# WAVE_RESHAPE.net
KiCad netlist of a schematic drawn in Altium Designer
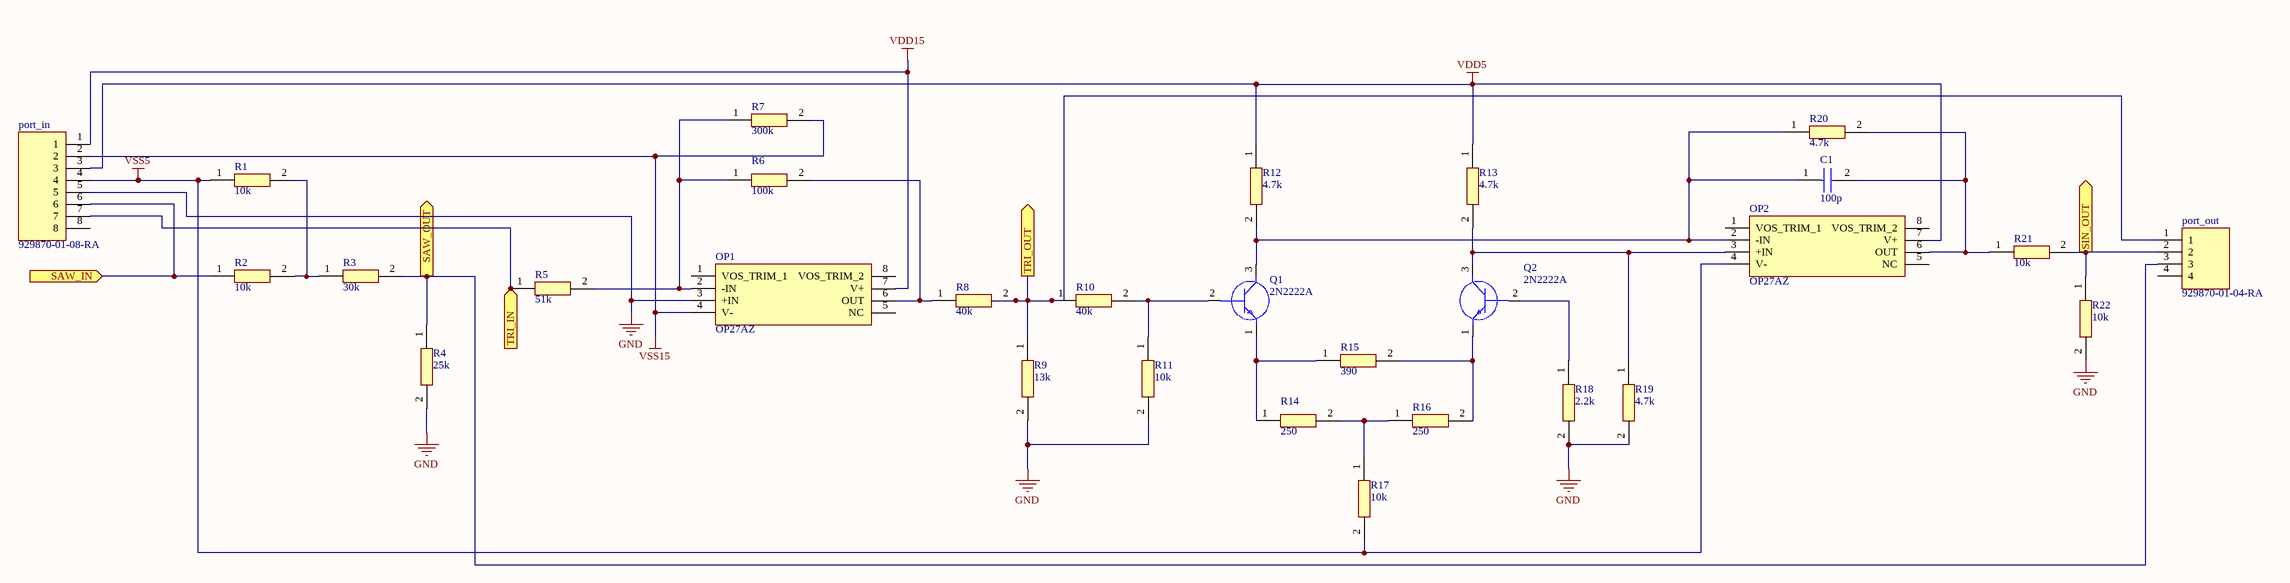
[diagram p0: WAVE_RESHAPE.SchDoc]

(export (version "E")
  (design (tool "Eeschema 10.0.6"))
  (components
    (comp (ref "C1")
      (value "100p")
      (footprint "SamacSys:CAPPA2400W30L800D400")
      (description "Capacitor")
      (fields (field (name "MANUFACTURER_PART_NUMBER") "0113207"))
      (libsource (lib "SamacSys") (part "0113207"))
    )
    (comp (ref "OP1")
      (value "OP27AZ")
      (footprint "SamacSys:DIP775W58P254L1029H508Q8N")
      (description "Integrated Circuit")
      (fields (field (name "MOUSER PART NUMBER") "700-OP27AZNR"))
      (libsource (lib "*") (part "OP27AZ"))
    )
    (comp (ref "OP2")
      (value "OP27AZ")
      (footprint "SamacSys:DIP775W58P254L1029H508Q8N")
      (description "Integrated Circuit")
      (fields (field (name "MOUSER PART NUMBER") "700-OP27AZNR"))
      (libsource (lib "SamacSys") (part "OP27AZ"))
    )
    (comp (ref "port_in")
      (value "929870-01-08-RA")
      (footprint "SamacSys:929870-01-08-RA")
      (description "Connector")
      (fields (field (name "MOUSER PART NUMBER") "517-929870-01-08-RA"))
      (libsource (lib "SamacSys") (part "929870-01-08-RA"))
    )
    (comp (ref "port_out")
      (value "929870-01-04-RA")
      (footprint "SamacSys:RHDR4W76P0X254_1X4_1016X254X826P")
      (description "Connector")
      (fields (field (name "MOUSER PART NUMBER") "517-929870-01-04-RA"))
      (libsource (lib "SamacSys") (part "929870-01-04-RA"))
    )
    (comp (ref "Q1")
      (value "2N2222A")
      (footprint "SamacSys:CENTRAL_TO18")
      (description "Transistor BJT NPN")
      (fields (field (name "MOUSER PART NUMBER") "610-2N2222A"))
      (libsource (lib "*") (part "2N2222A"))
    )
    (comp (ref "Q2")
      (value "2N2222A")
      (footprint "SamacSys:CENTRAL_TO18")
      (description "Transistor BJT NPN")
      (fields (field (name "MOUSER PART NUMBER") "610-2N2222A"))
      (libsource (lib "SamacSys") (part "2N2222A"))
    )
    (comp (ref "R1")
      (value "10k")
      (footprint "SamacSys:RESAD1650W60L650D250")
      (description "Resistor")
      (fields
        (field (name "MANUFACTURER_PART_NUMBER") "MRS25000C1003FC100")
        (field (name "MOUSER PART NUMBER") "594-MRS25000C1003FC1")
      )
      (libsource (lib "SamacSys") (part "MRS25000C1003FC100"))
    )
    (comp (ref "R2")
      (value "10k")
      (footprint "SamacSys:RESAD1650W60L650D250")
      (description "Resistor")
      (fields
        (field (name "MANUFACTURER_PART_NUMBER") "MRS25000C1003FC100")
        (field (name "MOUSER PART NUMBER") "594-MRS25000C1003FC1")
      )
      (libsource (lib "SamacSys") (part "MRS25000C1003FC100"))
    )
    (comp (ref "R3")
      (value "30k")
      (footprint "SamacSys:RESAD1650W60L650D250")
      (description "Resistor")
      (fields
        (field (name "MANUFACTURER_PART_NUMBER") "MRS25000C1003FC100")
        (field (name "MOUSER PART NUMBER") "594-MRS25000C1003FC1")
      )
      (libsource (lib "SamacSys") (part "MRS25000C1003FC100"))
    )
    (comp (ref "R4")
      (value "25k")
      (footprint "SamacSys:RESAD1650W60L650D250")
      (description "Resistor")
      (fields
        (field (name "MANUFACTURER_PART_NUMBER") "MRS25000C1003FC100")
        (field (name "MOUSER PART NUMBER") "594-MRS25000C1003FC1")
      )
      (libsource (lib "") (part "MRS25000C1003FC100_1"))
    )
    (comp (ref "R5")
      (value "51k")
      (footprint "SamacSys:RESAD1650W60L650D250")
      (description "Resistor")
      (fields
        (field (name "MANUFACTURER_PART_NUMBER") "MRS25000C1003FC100")
        (field (name "MOUSER PART NUMBER") "594-MRS25000C1003FC1")
      )
      (libsource (lib "SamacSys") (part "MRS25000C1003FC100"))
    )
    (comp (ref "R6")
      (value "100k")
      (footprint "SamacSys:RESAD1650W60L650D250")
      (description "Resistor")
      (fields
        (field (name "MANUFACTURER_PART_NUMBER") "MRS25000C1003FC100")
        (field (name "MOUSER PART NUMBER") "594-MRS25000C1003FC1")
      )
      (libsource (lib "SamacSys") (part "MRS25000C1003FC100"))
    )
    (comp (ref "R7")
      (value "300k")
      (footprint "SamacSys:RESAD1650W60L650D250")
      (description "Resistor")
      (fields
        (field (name "MANUFACTURER_PART_NUMBER") "MRS25000C1003FC100")
        (field (name "MOUSER PART NUMBER") "594-MRS25000C1003FC1")
      )
      (libsource (lib "SamacSys") (part "MRS25000C1003FC100"))
    )
    (comp (ref "R8")
      (value "40k")
      (footprint "SamacSys:RESAD1650W60L650D250")
      (description "Resistor")
      (fields
        (field (name "MANUFACTURER_PART_NUMBER") "MRS25000C1003FC100")
        (field (name "MOUSER PART NUMBER") "594-MRS25000C1003FC1")
      )
      (libsource (lib "SamacSys") (part "MRS25000C1003FC100"))
    )
    (comp (ref "R9")
      (value "13k")
      (footprint "SamacSys:RESAD1650W60L650D250")
      (description "Resistor")
      (fields
        (field (name "MANUFACTURER_PART_NUMBER") "MRS25000C1003FC100")
        (field (name "MOUSER PART NUMBER") "594-MRS25000C1003FC1")
      )
      (libsource (lib "") (part "MRS25000C1003FC100_1"))
    )
    (comp (ref "R10")
      (value "40k")
      (footprint "SamacSys:RESAD1650W60L650D250")
      (description "Resistor")
      (fields
        (field (name "MANUFACTURER_PART_NUMBER") "MRS25000C1003FC100")
        (field (name "MOUSER PART NUMBER") "594-MRS25000C1003FC1")
      )
      (libsource (lib "SamacSys") (part "MRS25000C1003FC100"))
    )
    (comp (ref "R11")
      (value "10k")
      (footprint "SamacSys:RESAD1650W60L650D250")
      (description "Resistor")
      (fields
        (field (name "MANUFACTURER_PART_NUMBER") "MRS25000C1003FC100")
        (field (name "MOUSER PART NUMBER") "594-MRS25000C1003FC1")
      )
      (libsource (lib "") (part "MRS25000C1003FC100_1"))
    )
    (comp (ref "R12")
      (value "4.7k")
      (footprint "SamacSys:RESAD1650W60L650D250")
      (description "Resistor")
      (fields
        (field (name "MANUFACTURER_PART_NUMBER") "MRS25000C1003FC100")
        (field (name "MOUSER PART NUMBER") "594-MRS25000C1003FC1")
      )
      (libsource (lib "") (part "MRS25000C1003FC100_1"))
    )
    (comp (ref "R13")
      (value "4.7k")
      (footprint "SamacSys:RESAD1650W60L650D250")
      (description "Resistor")
      (fields
        (field (name "MANUFACTURER_PART_NUMBER") "MRS25000C1003FC100")
        (field (name "MOUSER PART NUMBER") "594-MRS25000C1003FC1")
      )
      (libsource (lib "") (part "MRS25000C1003FC100_1"))
    )
    (comp (ref "R14")
      (value "250")
      (footprint "SamacSys:RESAD1650W60L650D250")
      (description "Resistor")
      (fields
        (field (name "MANUFACTURER_PART_NUMBER") "MRS25000C1003FC100")
        (field (name "MOUSER PART NUMBER") "594-MRS25000C1003FC1")
      )
      (libsource (lib "SamacSys") (part "MRS25000C1003FC100"))
    )
    (comp (ref "R15")
      (value "390")
      (footprint "SamacSys:RESAD1650W60L650D250")
      (description "Resistor")
      (fields
        (field (name "MANUFACTURER_PART_NUMBER") "MRS25000C1003FC100")
        (field (name "MOUSER PART NUMBER") "594-MRS25000C1003FC1")
      )
      (libsource (lib "SamacSys") (part "MRS25000C1003FC100"))
    )
    (comp (ref "R16")
      (value "250")
      (footprint "SamacSys:RESAD1650W60L650D250")
      (description "Resistor")
      (fields
        (field (name "MANUFACTURER_PART_NUMBER") "MRS25000C1003FC100")
        (field (name "MOUSER PART NUMBER") "594-MRS25000C1003FC1")
      )
      (libsource (lib "SamacSys") (part "MRS25000C1003FC100"))
    )
    (comp (ref "R17")
      (value "10k")
      (footprint "SamacSys:RESAD1650W60L650D250")
      (description "Resistor")
      (fields
        (field (name "MANUFACTURER_PART_NUMBER") "MRS25000C1003FC100")
        (field (name "MOUSER PART NUMBER") "594-MRS25000C1003FC1")
      )
      (libsource (lib "") (part "MRS25000C1003FC100_1"))
    )
    (comp (ref "R18")
      (value "2.2k")
      (footprint "SamacSys:RESAD1650W60L650D250")
      (description "Resistor")
      (fields
        (field (name "MANUFACTURER_PART_NUMBER") "MRS25000C1003FC100")
        (field (name "MOUSER PART NUMBER") "594-MRS25000C1003FC1")
      )
      (libsource (lib "") (part "MRS25000C1003FC100_1"))
    )
    (comp (ref "R19")
      (value "4.7k")
      (footprint "SamacSys:RESAD1650W60L650D250")
      (description "Resistor")
      (fields
        (field (name "MANUFACTURER_PART_NUMBER") "MRS25000C1003FC100")
        (field (name "MOUSER PART NUMBER") "594-MRS25000C1003FC1")
      )
      (libsource (lib "") (part "MRS25000C1003FC100_1"))
    )
    (comp (ref "R20")
      (value "4.7k")
      (footprint "SamacSys:RESAD1650W60L650D250")
      (description "Resistor")
      (fields
        (field (name "MANUFACTURER_PART_NUMBER") "MRS25000C1003FC100")
        (field (name "MOUSER PART NUMBER") "594-MRS25000C1003FC1")
      )
      (libsource (lib "SamacSys") (part "MRS25000C1003FC100"))
    )
    (comp (ref "R21")
      (value "10k")
      (footprint "SamacSys:RESAD1650W60L650D250")
      (description "Resistor")
      (fields
        (field (name "MANUFACTURER_PART_NUMBER") "MRS25000C1003FC100")
        (field (name "MOUSER PART NUMBER") "594-MRS25000C1003FC1")
      )
      (libsource (lib "SamacSys") (part "MRS25000C1003FC100"))
    )
    (comp (ref "R22")
      (value "10k")
      (footprint "SamacSys:RESAD1650W60L650D250")
      (description "Resistor")
      (fields
        (field (name "MANUFACTURER_PART_NUMBER") "MRS25000C1003FC100")
        (field (name "MOUSER PART NUMBER") "594-MRS25000C1003FC1")
      )
      (libsource (lib "") (part "MRS25000C1003FC100_1"))
    )
  )
  (nets
    (net (code "1") (name "/SAW_IN") (class "Default")
      (node (ref "R2") (pin "1") (pinfunction "1_1") (pintype "passive"))
      (node (ref "port_in") (pin "6") (pinfunction "6_6") (pintype "passive"))
    )
    (net (code "2") (name "/SAW_OUT") (class "Default")
      (node (ref "R3") (pin "2") (pinfunction "2_2") (pintype "passive"))
      (node (ref "R4") (pin "1") (pinfunction "1_1") (pintype "passive"))
      (node (ref "port_out") (pin "3") (pinfunction "3_3") (pintype "passive"))
    )
    (net (code "3") (name "/SIN_OUT") (class "Default")
      (node (ref "R21") (pin "2") (pinfunction "2_2") (pintype "passive"))
      (node (ref "R22") (pin "1") (pinfunction "1_1") (pintype "passive"))
      (node (ref "port_out") (pin "2") (pinfunction "2_2") (pintype "passive"))
    )
    (net (code "4") (name "/TRI_IN") (class "Default")
      (node (ref "R5") (pin "1") (pinfunction "1_1") (pintype "passive"))
      (node (ref "port_in") (pin "7") (pinfunction "7_7") (pintype "passive"))
    )
    (net (code "5") (name "/TRI_OUT") (class "Default")
      (node (ref "R10") (pin "1") (pinfunction "1_1") (pintype "passive"))
      (node (ref "R8") (pin "2") (pinfunction "2_2") (pintype "passive"))
      (node (ref "R9") (pin "1") (pinfunction "1_1") (pintype "passive"))
      (node (ref "port_out") (pin "1") (pinfunction "1_1") (pintype "passive"))
    )
    (net (code "6") (name "GND") (class "Default")
      (node (ref "OP1") (pin "3") (pinfunction "+IN_3") (pintype "passive"))
      (node (ref "R11") (pin "2") (pinfunction "2_2") (pintype "passive"))
      (node (ref "R18") (pin "2") (pinfunction "2_2") (pintype "passive"))
      (node (ref "R19") (pin "2") (pinfunction "2_2") (pintype "passive"))
      (node (ref "R22") (pin "2") (pinfunction "2_2") (pintype "passive"))
      (node (ref "R4") (pin "2") (pinfunction "2_2") (pintype "passive"))
      (node (ref "R9") (pin "2") (pinfunction "2_2") (pintype "passive"))
      (node (ref "port_in") (pin "5") (pinfunction "5_5") (pintype "passive"))
    )
    (net (code "7") (name "Net-(C1-+)") (class "Default")
      (node (ref "C1") (pin "1") (pinfunction "+_1") (pintype "passive"))
      (node (ref "OP2") (pin "2") (pinfunction "-IN_2") (pintype "passive"))
      (node (ref "Q1") (pin "3") (pinfunction "C_3") (pintype "passive"))
      (node (ref "R12") (pin "2") (pinfunction "2_2") (pintype "passive"))
      (node (ref "R20") (pin "1") (pinfunction "1_1") (pintype "passive"))
    )
    (net (code "8") (name "Net-(C1--)") (class "Default")
      (node (ref "C1") (pin "2") (pinfunction "-_2") (pintype "passive"))
      (node (ref "OP2") (pin "6") (pinfunction "OUT_6") (pintype "passive"))
      (node (ref "R20") (pin "2") (pinfunction "2_2") (pintype "passive"))
      (node (ref "R21") (pin "1") (pinfunction "1_1") (pintype "passive"))
    )
    (net (code "9") (name "Net-(OP1--IN)") (class "Default")
      (node (ref "OP1") (pin "2") (pinfunction "-IN_2") (pintype "passive"))
      (node (ref "R5") (pin "2") (pinfunction "2_2") (pintype "passive"))
      (node (ref "R6") (pin "1") (pinfunction "1_1") (pintype "passive"))
      (node (ref "R7") (pin "1") (pinfunction "1_1") (pintype "passive"))
    )
    (net (code "10") (name "Net-(OP1-OUT)") (class "Default")
      (node (ref "OP1") (pin "6") (pinfunction "OUT_6") (pintype "passive"))
      (node (ref "R6") (pin "2") (pinfunction "2_2") (pintype "passive"))
      (node (ref "R8") (pin "1") (pinfunction "1_1") (pintype "passive"))
    )
    (net (code "11") (name "Net-(OP2-+IN)") (class "Default")
      (node (ref "OP2") (pin "3") (pinfunction "+IN_3") (pintype "passive"))
      (node (ref "Q2") (pin "3") (pinfunction "C_3") (pintype "passive"))
      (node (ref "R13") (pin "2") (pinfunction "2_2") (pintype "passive"))
      (node (ref "R19") (pin "1") (pinfunction "1_1") (pintype "passive"))
    )
    (net (code "12") (name "Net-(Q1-B)") (class "Default")
      (node (ref "Q1") (pin "2") (pinfunction "B_2") (pintype "passive"))
      (node (ref "R10") (pin "2") (pinfunction "2_2") (pintype "passive"))
      (node (ref "R11") (pin "1") (pinfunction "1_1") (pintype "passive"))
    )
    (net (code "13") (name "Net-(Q1-E)") (class "Default")
      (node (ref "Q1") (pin "1") (pinfunction "E_1") (pintype "passive"))
      (node (ref "R14") (pin "1") (pinfunction "1_1") (pintype "passive"))
      (node (ref "R15") (pin "1") (pinfunction "1_1") (pintype "passive"))
    )
    (net (code "14") (name "Net-(Q2-B)") (class "Default")
      (node (ref "Q2") (pin "2") (pinfunction "B_2") (pintype "passive"))
      (node (ref "R18") (pin "1") (pinfunction "1_1") (pintype "passive"))
    )
    (net (code "15") (name "Net-(Q2-E)") (class "Default")
      (node (ref "Q2") (pin "1") (pinfunction "E_1") (pintype "passive"))
      (node (ref "R15") (pin "2") (pinfunction "2_2") (pintype "passive"))
      (node (ref "R16") (pin "2") (pinfunction "2_2") (pintype "passive"))
    )
    (net (code "16") (name "Net-(R1-Pad2)") (class "Default")
      (node (ref "R1") (pin "2") (pinfunction "2_2") (pintype "passive"))
      (node (ref "R2") (pin "2") (pinfunction "2_2") (pintype "passive"))
      (node (ref "R3") (pin "1") (pinfunction "1_1") (pintype "passive"))
    )
    (net (code "17") (name "Net-(R14-Pad2)") (class "Default")
      (node (ref "R14") (pin "2") (pinfunction "2_2") (pintype "passive"))
      (node (ref "R16") (pin "1") (pinfunction "1_1") (pintype "passive"))
      (node (ref "R17") (pin "1") (pinfunction "1_1") (pintype "passive"))
    )
    (net (code "18") (name "VDD5") (class "Default")
      (node (ref "OP2") (pin "7") (pinfunction "V+_7") (pintype "passive"))
      (node (ref "R12") (pin "1") (pinfunction "1_1") (pintype "passive"))
      (node (ref "R13") (pin "1") (pinfunction "1_1") (pintype "passive"))
      (node (ref "port_in") (pin "3") (pinfunction "3_3") (pintype "passive"))
    )
    (net (code "19") (name "VDD15") (class "Default")
      (node (ref "OP1") (pin "7") (pinfunction "V+_7") (pintype "passive"))
      (node (ref "port_in") (pin "1") (pinfunction "1_1") (pintype "passive"))
    )
    (net (code "20") (name "VSS5") (class "Default")
      (node (ref "OP2") (pin "4") (pinfunction "V-_4") (pintype "passive"))
      (node (ref "R1") (pin "1") (pinfunction "1_1") (pintype "passive"))
      (node (ref "R17") (pin "2") (pinfunction "2_2") (pintype "passive"))
      (node (ref "port_in") (pin "4") (pinfunction "4_4") (pintype "passive"))
    )
    (net (code "21") (name "VSS15") (class "Default")
      (node (ref "OP1") (pin "4") (pinfunction "V-_4") (pintype "passive"))
      (node (ref "R7") (pin "2") (pinfunction "2_2") (pintype "passive"))
      (node (ref "port_in") (pin "2") (pinfunction "2_2") (pintype "passive"))
    )
    (net (code "22") (name "unconnected-(OP1-NC-Pad5)") (class "Default")
      (node (ref "OP1") (pin "5") (pinfunction "NC_5") (pintype "passive"))
    )
    (net (code "23") (name "unconnected-(OP1-VOS_TRIM_1-Pad1)") (class "Default")
      (node (ref "OP1") (pin "1") (pinfunction "VOS_TRIM_1_1") (pintype "passive"))
    )
    (net (code "24") (name "unconnected-(OP1-VOS_TRIM_2-Pad8)") (class "Default")
      (node (ref "OP1") (pin "8") (pinfunction "VOS_TRIM_2_8") (pintype "passive"))
    )
    (net (code "25") (name "unconnected-(OP2-NC-Pad5)") (class "Default")
      (node (ref "OP2") (pin "5") (pinfunction "NC_5") (pintype "passive"))
    )
    (net (code "26") (name "unconnected-(OP2-VOS_TRIM_1-Pad1)") (class "Default")
      (node (ref "OP2") (pin "1") (pinfunction "VOS_TRIM_1_1") (pintype "passive"))
    )
    (net (code "27") (name "unconnected-(OP2-VOS_TRIM_2-Pad8)") (class "Default")
      (node (ref "OP2") (pin "8") (pinfunction "VOS_TRIM_2_8") (pintype "passive"))
    )
    (net (code "28") (name "unconnected-(port_in-Pad8)") (class "Default")
      (node (ref "port_in") (pin "8") (pinfunction "8_8") (pintype "passive"))
    )
    (net (code "29") (name "unconnected-(port_out-Pad4)") (class "Default")
      (node (ref "port_out") (pin "4") (pinfunction "4_4") (pintype "passive"))
    )
  )
)
